# 01_POWER.net
KiCad netlist of a schematic drawn in Altium Designer
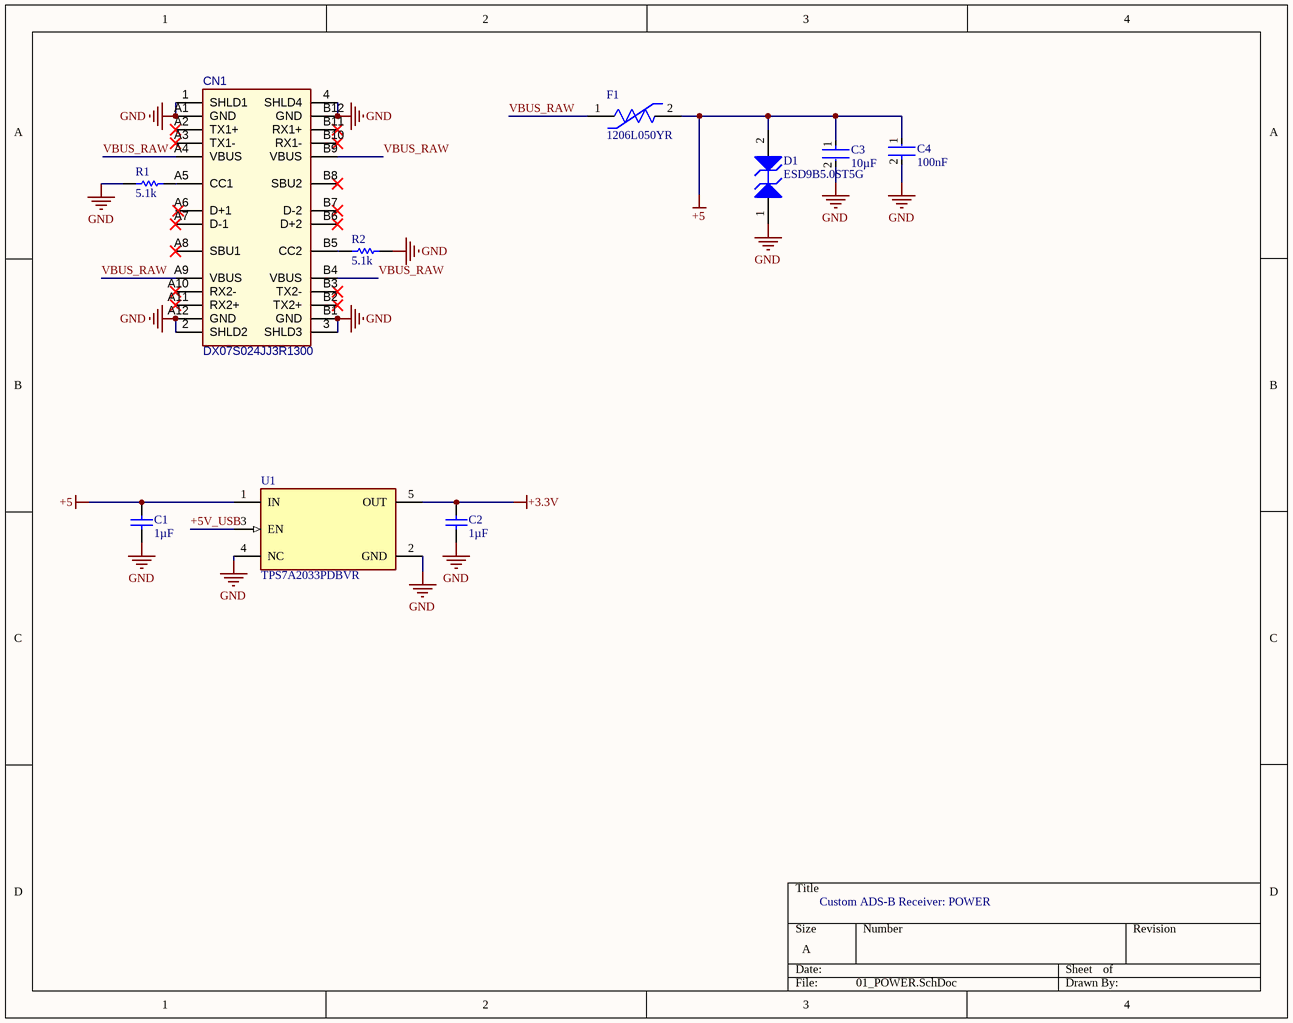
[diagram p0: 01_POWER.SchDoc]

(export (version "E")
  (design (tool "Eeschema 10.0.6"))
  (components
    (comp (ref "C1")
      (value "1µF")
      (footprint "RESC1608X100N")
      (description "0603 1 uF 10 V ±10% Tolerance X5R SMT Multilayer Ceramic Capacitor")
      (fields (field (name "TOLERANCE") "10%") (field (name "Comment") "GRM188R61A105KA61D"))
      (libsource (lib "Maksym Pleshyvtsev") (part "CAP-NP-2"))
    )
    (comp (ref "C2")
      (value "1µF")
      (footprint "RESC1608X100N")
      (description "0603 1 uF 10 V ±10% Tolerance X5R SMT Multilayer Ceramic Capacitor")
      (fields (field (name "TOLERANCE") "10%") (field (name "Comment") "GRM188R61A105KA61D"))
      (libsource (lib "Maksym Pleshyvtsev") (part "CAP-NP-2"))
    )
    (comp (ref "C3")
      (value "10µF")
      (footprint "FP-GRM18-0_15-MFG")
      (description "Multilayer Ceramic Capacitor, 10 uF, 10 V, ± 10%, X5R, 0603 [1608 Metric]")
      (fields (field (name "TOLERANCE") "10%") (field (name "Comment") "GRM188R61A106KE69D"))
      (libsource (lib "Maksym Pleshyvtsev") (part "11868f565c42a9108669ba33697ecf6"))
    )
    (comp (ref "C4")
      (value "100nF")
      (footprint "FP-GRM15-MFG")
      (description "16V 100nF X7R ±10% 0402 Multilayer Ceramic Capacitors MLCC - SMD/SMT ROHS")
      (fields (field (name "TOLERANCE") "10%") (field (name "Comment") "GRM155R71C104KA88D"))
      (libsource (lib "Maksym Pleshyvtsev") (part "236180d848d6139a670b325ea6854c9"))
    )
    (comp (ref "CN1")
      (value "DX07S024JJ3R1300")
      (footprint "JAE-DX07S024JJ3_V")
      (description "USB-C Connector, 20 V, 1.25 A, -30 to 80 degC, RoHS, Tape and Reel")
      (libsource (lib "Maksym Pleshyvtsev") (part "CMP-00171-5"))
    )
    (comp (ref "D1")
      (value "ESD9B5.0ST5G")
      (footprint "ONSC-SOD-923-2-514AB-01_V")
      (description "Tvs Diodes & Esd Suppressors; ESD9B5.0ST5G; on Semiconductor; 5 V; 2; 15 V; 5.8 V")
      (libsource (lib "Maksym Pleshyvtsev") (part "ONSC-A1A2-2"))
    )
    (comp (ref "F1")
      (value "1206L050YR")
      (footprint "FP-1206L050YR-MFG")
      (description "PTC Resettable Fuse 0.5A(hold) 1A(trip) 6VDC 100A 0.6W 0.1s 0.15Ohm SMD Solder Pad 1206 T/R")
      (libsource (lib "Maksym Pleshyvtsev") (part "fdf083d5f6389a9a1c4e51137f46658"))
    )
    (comp (ref "R1")
      (value "5.1k")
      (footprint "RESC1005X40X25NL05T10")
      (description "62.5mW Thick Film Resistors 50V ±100ppm/℃ ±1% 5.1kΩ 0402 Chip Resistor - Surface Mount ROHS")
      (fields (field (name "TOLERANCE") "1%") (field (name "Comment") "RC0402FR-075K1L"))
      (libsource (lib "Maksym Pleshyvtsev") (part "RES"))
    )
    (comp (ref "R2")
      (value "5.1k")
      (footprint "RESC1005X40X25NL05T10")
      (description "62.5mW Thick Film Resistors 50V ±100ppm/℃ ±1% 5.1kΩ 0402 Chip Resistor - Surface Mount ROHS")
      (fields (field (name "TOLERANCE") "1%") (field (name "Comment") "RC0402FR-075K1L"))
      (libsource (lib "Maksym Pleshyvtsev") (part "RES"))
    )
    (comp (ref "U1")
      (value "TPS7A2033PDBVR")
      (footprint "FP-DBV0005A-MFG")
      (description "300mA ultra-low-noise low-IQ low-dropout (LDO) linear regulator with high PSRR 5-SOT-23 -40 to 125")
      (libsource (lib "Maksym Pleshyvtsev") (part "76aa7ad0ceb1012e0d85aeafc53095f"))
    )
  )
  (nets
    (net (code "1") (name "+3.3V") (class "Default")
      (node (ref "C2") (pin "2") (pinfunction "2_2") (pintype "passive"))
      (node (ref "U1") (pin "5") (pinfunction "OUT_5") (pintype "passive"))
    )
    (net (code "2") (name "+5") (class "Default")
      (node (ref "C1") (pin "2") (pinfunction "2_2") (pintype "passive"))
      (node (ref "C3") (pin "1") (pinfunction "1_1") (pintype "passive"))
      (node (ref "C4") (pin "1") (pinfunction "1_1") (pintype "passive"))
      (node (ref "D1") (pin "2") (pinfunction "A2_2") (pintype "passive"))
      (node (ref "F1") (pin "2") (pinfunction "2_2") (pintype "passive"))
      (node (ref "U1") (pin "1") (pinfunction "IN_1") (pintype "power_in"))
    )
    (net (code "3") (name "/+5V_USB") (class "Default")
      (node (ref "U1") (pin "3") (pinfunction "EN_3") (pintype "input"))
    )
    (net (code "4") (name "/VBUS_RAW") (class "Default")
      (node (ref "CN1") (pin "A4") (pinfunction "VBUS_A4") (pintype "passive"))
      (node (ref "CN1") (pin "A9") (pinfunction "VBUS_A9") (pintype "passive"))
      (node (ref "CN1") (pin "B4") (pinfunction "VBUS_B4") (pintype "passive"))
      (node (ref "CN1") (pin "B9") (pinfunction "VBUS_B9") (pintype "passive"))
      (node (ref "F1") (pin "1") (pinfunction "1_1") (pintype "passive"))
    )
    (net (code "5") (name "GND") (class "Default")
      (node (ref "C1") (pin "1") (pinfunction "1_1") (pintype "passive"))
      (node (ref "C2") (pin "1") (pinfunction "1_1") (pintype "passive"))
      (node (ref "C3") (pin "2") (pinfunction "2_2") (pintype "passive"))
      (node (ref "C4") (pin "2") (pinfunction "2_2") (pintype "passive"))
      (node (ref "CN1") (pin "1") (pinfunction "SHLD1_1") (pintype "passive"))
      (node (ref "CN1") (pin "2") (pinfunction "SHLD2_2") (pintype "passive"))
      (node (ref "CN1") (pin "3") (pinfunction "SHLD3_3") (pintype "passive"))
      (node (ref "CN1") (pin "4") (pinfunction "SHLD4_4") (pintype "passive"))
      (node (ref "CN1") (pin "A1") (pinfunction "GND_A1") (pintype "passive"))
      (node (ref "CN1") (pin "A12") (pinfunction "GND_A12") (pintype "passive"))
      (node (ref "CN1") (pin "B1") (pinfunction "GND_B1") (pintype "passive"))
      (node (ref "CN1") (pin "B12") (pinfunction "GND_B12") (pintype "passive"))
      (node (ref "D1") (pin "1") (pinfunction "A1_1") (pintype "passive"))
      (node (ref "R1") (pin "1") (pinfunction "1_1") (pintype "passive"))
      (node (ref "R2") (pin "2") (pinfunction "2_2") (pintype "passive"))
      (node (ref "U1") (pin "2") (pinfunction "GND_2") (pintype "power_in"))
      (node (ref "U1") (pin "4") (pinfunction "NC_4") (pintype "passive"))
    )
    (net (code "6") (name "Net-(CN1-CC1)") (class "Default")
      (node (ref "CN1") (pin "A5") (pinfunction "CC1_A5") (pintype "passive"))
      (node (ref "R1") (pin "2") (pinfunction "2_2") (pintype "passive"))
    )
    (net (code "7") (name "Net-(CN1-CC2)") (class "Default")
      (node (ref "CN1") (pin "B5") (pinfunction "CC2_B5") (pintype "passive"))
      (node (ref "R2") (pin "1") (pinfunction "1_1") (pintype "passive"))
    )
    (net (code "8") (name "unconnected-(CN1-D+1-PadA6)") (class "Default")
      (node (ref "CN1") (pin "A6") (pinfunction "D+1_A6") (pintype "passive"))
    )
    (net (code "9") (name "unconnected-(CN1-D+2-PadB6)") (class "Default")
      (node (ref "CN1") (pin "B6") (pinfunction "D+2_B6") (pintype "passive+no_connect"))
    )
    (net (code "10") (name "unconnected-(CN1-D-1-PadA7)") (class "Default")
      (node (ref "CN1") (pin "A7") (pinfunction "D-1_A7") (pintype "passive+no_connect"))
    )
    (net (code "11") (name "unconnected-(CN1-D-2-PadB7)") (class "Default")
      (node (ref "CN1") (pin "B7") (pinfunction "D-2_B7") (pintype "passive+no_connect"))
    )
    (net (code "12") (name "unconnected-(CN1-RX1+-PadB11)") (class "Default")
      (node (ref "CN1") (pin "B11") (pinfunction "RX1+_B11") (pintype "passive+no_connect"))
    )
    (net (code "13") (name "unconnected-(CN1-RX1--PadB10)") (class "Default")
      (node (ref "CN1") (pin "B10") (pinfunction "RX1-_B10") (pintype "passive+no_connect"))
    )
    (net (code "14") (name "unconnected-(CN1-RX2+-PadA11)") (class "Default")
      (node (ref "CN1") (pin "A11") (pinfunction "RX2+_A11") (pintype "passive+no_connect"))
    )
    (net (code "15") (name "unconnected-(CN1-RX2--PadA10)") (class "Default")
      (node (ref "CN1") (pin "A10") (pinfunction "RX2-_A10") (pintype "passive+no_connect"))
    )
    (net (code "16") (name "unconnected-(CN1-SBU1-PadA8)") (class "Default")
      (node (ref "CN1") (pin "A8") (pinfunction "SBU1_A8") (pintype "passive+no_connect"))
    )
    (net (code "17") (name "unconnected-(CN1-SBU2-PadB8)") (class "Default")
      (node (ref "CN1") (pin "B8") (pinfunction "SBU2_B8") (pintype "passive+no_connect"))
    )
    (net (code "18") (name "unconnected-(CN1-TX1+-PadA2)") (class "Default")
      (node (ref "CN1") (pin "A2") (pinfunction "TX1+_A2") (pintype "passive+no_connect"))
    )
    (net (code "19") (name "unconnected-(CN1-TX1--PadA3)") (class "Default")
      (node (ref "CN1") (pin "A3") (pinfunction "TX1-_A3") (pintype "passive+no_connect"))
    )
    (net (code "20") (name "unconnected-(CN1-TX2+-PadB2)") (class "Default")
      (node (ref "CN1") (pin "B2") (pinfunction "TX2+_B2") (pintype "passive+no_connect"))
    )
    (net (code "21") (name "unconnected-(CN1-TX2--PadB3)") (class "Default")
      (node (ref "CN1") (pin "B3") (pinfunction "TX2-_B3") (pintype "passive+no_connect"))
    )
  )
)
